# rpi-adapter_V0.net
KiCad netlist of a schematic drawn in EAGLE
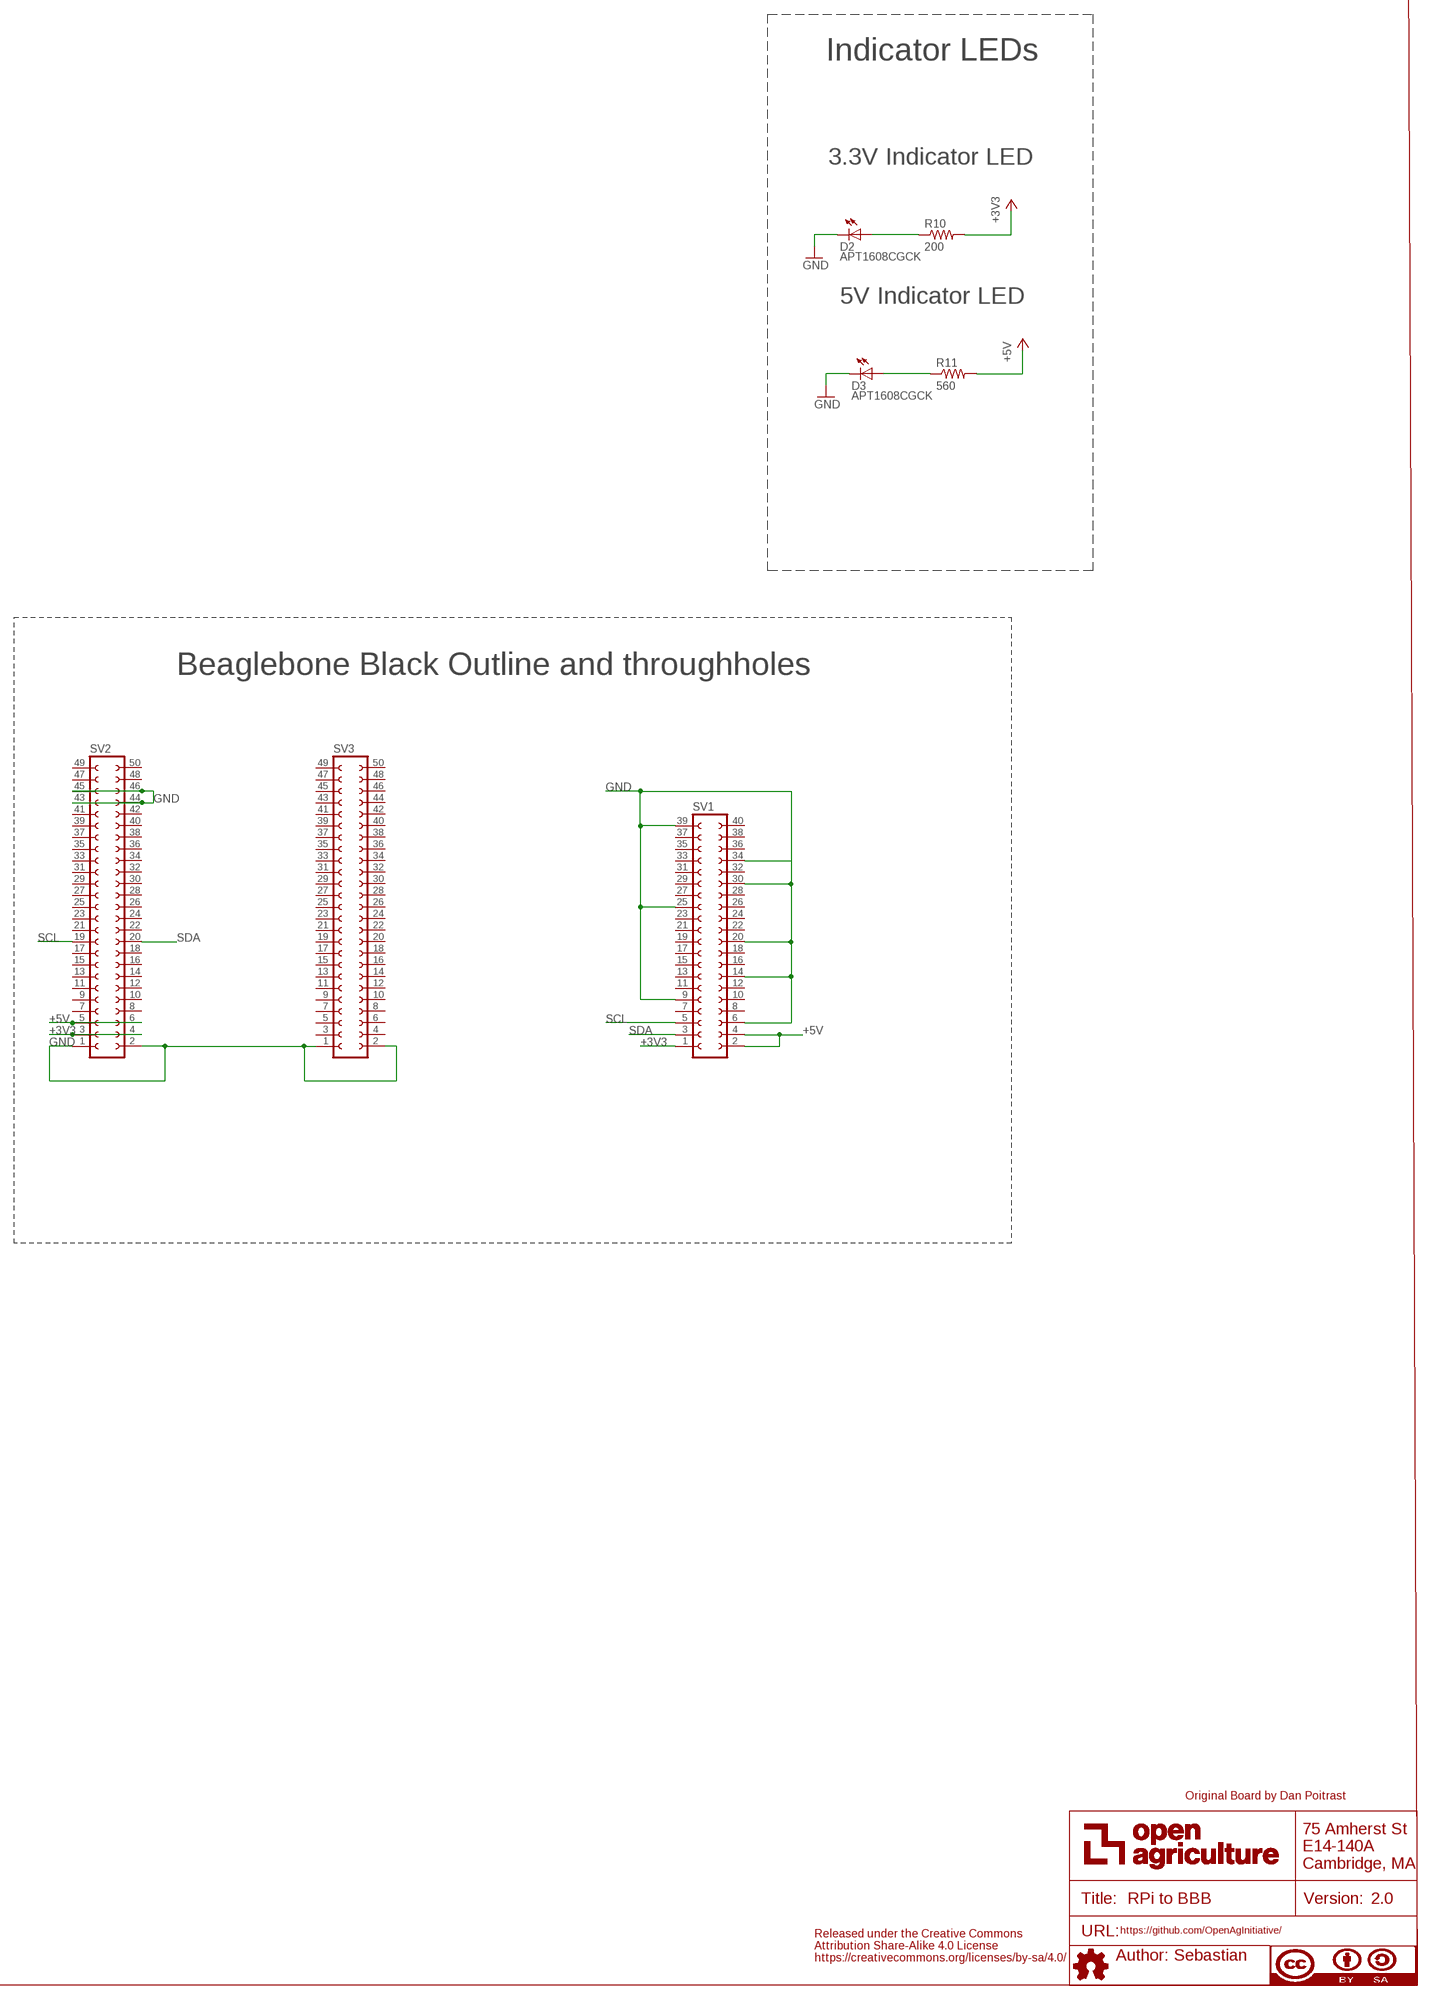
[diagram p0: schematic, sheet 1]

(export (version "E")
  (design (tool "Eeschema 10.0.6"))
  (components
    (comp (ref "ATTRIBUTES")
      (value "DOCFIELD")
      (footprint "eagle-import:DOCFIELD")
      (description "RPi to BBB")
      (fields
        (field (name "TITLE") "Example Template")
        (field (name "AUTHOR") "XX")
        (field (name "VER") "1.0")
        (field (name "URL") "https://github.com/OpenAgInitiative/openag_eagle_template")
        (field (name "AUTHOR_1") "Sebastian")
        (field (name "TITLE_1") "RPi to BBB")
        (field (name "URL_1") "https://github.com/OpenAgInitiative/")
        (field (name "VER_1") "2.0")
      )
      (libsource (lib "eagle-import") (part "DOCFIELD"))
    )
    (comp (ref "D2")
      (value "APT1608CGCK")
      (footprint "eagle-import:CHIPLED_0603")
      (libsource (lib "eagle-import") (part "APT1608CGCK"))
    )
    (comp (ref "D3")
      (value "APT1608CGCK")
      (footprint "eagle-import:CHIPLED_0603")
      (libsource (lib "eagle-import") (part "APT1608CGCK"))
    )
    (comp (ref "R10")
      (value "200")
      (footprint "eagle-import:RC0603N")
      (libsource (lib "eagle-import") (part "100OHM-RC0603JR-07100RL"))
    )
    (comp (ref "R11")
      (value "560")
      (footprint "eagle-import:RC0603N")
      (libsource (lib "eagle-import") (part "100OHM-RC0603JR-07100RL"))
    )
    (comp (ref "SV1")
      (value "FE20-2")
      (footprint "eagle-import:FE20-2")
      (libsource (lib "eagle-import") (part "FE20-2"))
    )
    (comp (ref "SV2")
      (value "FE25-2")
      (footprint "eagle-import:FE25-2")
      (libsource (lib "eagle-import") (part "FE25-2"))
    )
    (comp (ref "SV3")
      (value "FE25-2")
      (footprint "eagle-import:FE25-2")
      (libsource (lib "eagle-import") (part "FE25-2"))
    )
  )
  (nets
    (net (code "1") (name "+3V3") (class "Default")
      (node (ref "R10") (pin "2") (pinfunction "2_2") (pintype "passive"))
      (node (ref "SV1") (pin "1") (pinfunction "1_1") (pintype "passive"))
      (node (ref "SV2") (pin "3") (pinfunction "3_3") (pintype "passive"))
      (node (ref "SV2") (pin "4") (pinfunction "4_4") (pintype "passive"))
    )
    (net (code "2") (name "+5V") (class "Default")
      (node (ref "R11") (pin "2") (pinfunction "2_2") (pintype "passive"))
      (node (ref "SV1") (pin "2") (pinfunction "2_2") (pintype "passive"))
      (node (ref "SV1") (pin "4") (pinfunction "4_4") (pintype "passive"))
      (node (ref "SV2") (pin "5") (pinfunction "5_5") (pintype "passive"))
      (node (ref "SV2") (pin "6") (pinfunction "6_6") (pintype "passive"))
    )
    (net (code "3") (name "/SCL") (class "Default")
      (node (ref "SV1") (pin "5") (pinfunction "5_5") (pintype "passive"))
      (node (ref "SV2") (pin "19") (pinfunction "19_19") (pintype "passive"))
    )
    (net (code "4") (name "/SDA") (class "Default")
      (node (ref "SV1") (pin "3") (pinfunction "3_3") (pintype "passive"))
      (node (ref "SV2") (pin "20") (pinfunction "20_20") (pintype "passive"))
    )
    (net (code "5") (name "GND") (class "Default")
      (node (ref "D2") (pin "C") (pinfunction "C_C") (pintype "passive"))
      (node (ref "D3") (pin "C") (pinfunction "C_C") (pintype "passive"))
      (node (ref "SV1") (pin "14") (pinfunction "14_14") (pintype "passive"))
      (node (ref "SV1") (pin "20") (pinfunction "20_20") (pintype "passive"))
      (node (ref "SV1") (pin "25") (pinfunction "25_25") (pintype "passive"))
      (node (ref "SV1") (pin "30") (pinfunction "30_30") (pintype "passive"))
      (node (ref "SV1") (pin "34") (pinfunction "34_34") (pintype "passive"))
      (node (ref "SV1") (pin "39") (pinfunction "39_39") (pintype "passive"))
      (node (ref "SV1") (pin "6") (pinfunction "6_6") (pintype "passive"))
      (node (ref "SV1") (pin "9") (pinfunction "9_9") (pintype "passive"))
      (node (ref "SV2") (pin "1") (pinfunction "1_1") (pintype "passive"))
      (node (ref "SV2") (pin "2") (pinfunction "2_2") (pintype "passive"))
      (node (ref "SV2") (pin "43") (pinfunction "43_43") (pintype "passive"))
      (node (ref "SV2") (pin "44") (pinfunction "44_44") (pintype "passive"))
      (node (ref "SV2") (pin "45") (pinfunction "45_45") (pintype "passive"))
      (node (ref "SV2") (pin "46") (pinfunction "46_46") (pintype "passive"))
      (node (ref "SV3") (pin "1") (pinfunction "1_1") (pintype "passive"))
      (node (ref "SV3") (pin "2") (pinfunction "2_2") (pintype "passive"))
    )
    (net (code "6") (name "Net-(D2-PadA)") (class "Default")
      (node (ref "D2") (pin "A") (pinfunction "A_A") (pintype "passive"))
      (node (ref "R10") (pin "1") (pinfunction "1_1") (pintype "passive"))
    )
    (net (code "7") (name "Net-(D3-PadA)") (class "Default")
      (node (ref "D3") (pin "A") (pinfunction "A_A") (pintype "passive"))
      (node (ref "R11") (pin "1") (pinfunction "1_1") (pintype "passive"))
    )
    (net (code "8") (name "unconnected-(SV1-Pad7)") (class "Default")
      (node (ref "SV1") (pin "7") (pinfunction "7_7") (pintype "passive"))
    )
    (net (code "9") (name "unconnected-(SV1-Pad8)") (class "Default")
      (node (ref "SV1") (pin "8") (pinfunction "8_8") (pintype "passive"))
    )
    (net (code "10") (name "unconnected-(SV1-Pad10)") (class "Default")
      (node (ref "SV1") (pin "10") (pinfunction "10_10") (pintype "passive"))
    )
    (net (code "11") (name "unconnected-(SV1-Pad11)") (class "Default")
      (node (ref "SV1") (pin "11") (pinfunction "11_11") (pintype "passive"))
    )
    (net (code "12") (name "unconnected-(SV1-Pad12)") (class "Default")
      (node (ref "SV1") (pin "12") (pinfunction "12_12") (pintype "passive"))
    )
    (net (code "13") (name "unconnected-(SV1-Pad13)") (class "Default")
      (node (ref "SV1") (pin "13") (pinfunction "13_13") (pintype "passive"))
    )
    (net (code "14") (name "unconnected-(SV1-Pad15)") (class "Default")
      (node (ref "SV1") (pin "15") (pinfunction "15_15") (pintype "passive"))
    )
    (net (code "15") (name "unconnected-(SV1-Pad16)") (class "Default")
      (node (ref "SV1") (pin "16") (pinfunction "16_16") (pintype "passive"))
    )
    (net (code "16") (name "unconnected-(SV1-Pad17)") (class "Default")
      (node (ref "SV1") (pin "17") (pinfunction "17_17") (pintype "passive"))
    )
    (net (code "17") (name "unconnected-(SV1-Pad18)") (class "Default")
      (node (ref "SV1") (pin "18") (pinfunction "18_18") (pintype "passive"))
    )
    (net (code "18") (name "unconnected-(SV1-Pad19)") (class "Default")
      (node (ref "SV1") (pin "19") (pinfunction "19_19") (pintype "passive"))
    )
    (net (code "19") (name "unconnected-(SV1-Pad21)") (class "Default")
      (node (ref "SV1") (pin "21") (pinfunction "21_21") (pintype "passive"))
    )
    (net (code "20") (name "unconnected-(SV1-Pad22)") (class "Default")
      (node (ref "SV1") (pin "22") (pinfunction "22_22") (pintype "passive"))
    )
    (net (code "21") (name "unconnected-(SV1-Pad23)") (class "Default")
      (node (ref "SV1") (pin "23") (pinfunction "23_23") (pintype "passive"))
    )
    (net (code "22") (name "unconnected-(SV1-Pad24)") (class "Default")
      (node (ref "SV1") (pin "24") (pinfunction "24_24") (pintype "passive"))
    )
    (net (code "23") (name "unconnected-(SV1-Pad26)") (class "Default")
      (node (ref "SV1") (pin "26") (pinfunction "26_26") (pintype "passive"))
    )
    (net (code "24") (name "unconnected-(SV1-Pad27)") (class "Default")
      (node (ref "SV1") (pin "27") (pinfunction "27_27") (pintype "passive"))
    )
    (net (code "25") (name "unconnected-(SV1-Pad28)") (class "Default")
      (node (ref "SV1") (pin "28") (pinfunction "28_28") (pintype "passive"))
    )
    (net (code "26") (name "unconnected-(SV1-Pad29)") (class "Default")
      (node (ref "SV1") (pin "29") (pinfunction "29_29") (pintype "passive"))
    )
    (net (code "27") (name "unconnected-(SV1-Pad31)") (class "Default")
      (node (ref "SV1") (pin "31") (pinfunction "31_31") (pintype "passive"))
    )
    (net (code "28") (name "unconnected-(SV1-Pad32)") (class "Default")
      (node (ref "SV1") (pin "32") (pinfunction "32_32") (pintype "passive"))
    )
    (net (code "29") (name "unconnected-(SV1-Pad33)") (class "Default")
      (node (ref "SV1") (pin "33") (pinfunction "33_33") (pintype "passive"))
    )
    (net (code "30") (name "unconnected-(SV1-Pad35)") (class "Default")
      (node (ref "SV1") (pin "35") (pinfunction "35_35") (pintype "passive"))
    )
    (net (code "31") (name "unconnected-(SV1-Pad36)") (class "Default")
      (node (ref "SV1") (pin "36") (pinfunction "36_36") (pintype "passive"))
    )
    (net (code "32") (name "unconnected-(SV1-Pad37)") (class "Default")
      (node (ref "SV1") (pin "37") (pinfunction "37_37") (pintype "passive"))
    )
    (net (code "33") (name "unconnected-(SV1-Pad38)") (class "Default")
      (node (ref "SV1") (pin "38") (pinfunction "38_38") (pintype "passive"))
    )
    (net (code "34") (name "unconnected-(SV1-Pad40)") (class "Default")
      (node (ref "SV1") (pin "40") (pinfunction "40_40") (pintype "passive"))
    )
    (net (code "35") (name "unconnected-(SV2-Pad7)") (class "Default")
      (node (ref "SV2") (pin "7") (pinfunction "7_7") (pintype "passive"))
    )
    (net (code "36") (name "unconnected-(SV2-Pad8)") (class "Default")
      (node (ref "SV2") (pin "8") (pinfunction "8_8") (pintype "passive"))
    )
    (net (code "37") (name "unconnected-(SV2-Pad9)") (class "Default")
      (node (ref "SV2") (pin "9") (pinfunction "9_9") (pintype "passive"))
    )
    (net (code "38") (name "unconnected-(SV2-Pad10)") (class "Default")
      (node (ref "SV2") (pin "10") (pinfunction "10_10") (pintype "passive"))
    )
    (net (code "39") (name "unconnected-(SV2-Pad11)") (class "Default")
      (node (ref "SV2") (pin "11") (pinfunction "11_11") (pintype "passive"))
    )
    (net (code "40") (name "unconnected-(SV2-Pad12)") (class "Default")
      (node (ref "SV2") (pin "12") (pinfunction "12_12") (pintype "passive"))
    )
    (net (code "41") (name "unconnected-(SV2-Pad13)") (class "Default")
      (node (ref "SV2") (pin "13") (pinfunction "13_13") (pintype "passive"))
    )
    (net (code "42") (name "unconnected-(SV2-Pad14)") (class "Default")
      (node (ref "SV2") (pin "14") (pinfunction "14_14") (pintype "passive"))
    )
    (net (code "43") (name "unconnected-(SV2-Pad15)") (class "Default")
      (node (ref "SV2") (pin "15") (pinfunction "15_15") (pintype "passive"))
    )
    (net (code "44") (name "unconnected-(SV2-Pad16)") (class "Default")
      (node (ref "SV2") (pin "16") (pinfunction "16_16") (pintype "passive"))
    )
    (net (code "45") (name "unconnected-(SV2-Pad17)") (class "Default")
      (node (ref "SV2") (pin "17") (pinfunction "17_17") (pintype "passive"))
    )
    (net (code "46") (name "unconnected-(SV2-Pad18)") (class "Default")
      (node (ref "SV2") (pin "18") (pinfunction "18_18") (pintype "passive"))
    )
    (net (code "47") (name "unconnected-(SV2-Pad21)") (class "Default")
      (node (ref "SV2") (pin "21") (pinfunction "21_21") (pintype "passive"))
    )
    (net (code "48") (name "unconnected-(SV2-Pad22)") (class "Default")
      (node (ref "SV2") (pin "22") (pinfunction "22_22") (pintype "passive"))
    )
    (net (code "49") (name "unconnected-(SV2-Pad23)") (class "Default")
      (node (ref "SV2") (pin "23") (pinfunction "23_23") (pintype "passive"))
    )
    (net (code "50") (name "unconnected-(SV2-Pad24)") (class "Default")
      (node (ref "SV2") (pin "24") (pinfunction "24_24") (pintype "passive"))
    )
    (net (code "51") (name "unconnected-(SV2-Pad25)") (class "Default")
      (node (ref "SV2") (pin "25") (pinfunction "25_25") (pintype "passive"))
    )
    (net (code "52") (name "unconnected-(SV2-Pad26)") (class "Default")
      (node (ref "SV2") (pin "26") (pinfunction "26_26") (pintype "passive"))
    )
    (net (code "53") (name "unconnected-(SV2-Pad27)") (class "Default")
      (node (ref "SV2") (pin "27") (pinfunction "27_27") (pintype "passive"))
    )
    (net (code "54") (name "unconnected-(SV2-Pad28)") (class "Default")
      (node (ref "SV2") (pin "28") (pinfunction "28_28") (pintype "passive"))
    )
    (net (code "55") (name "unconnected-(SV2-Pad29)") (class "Default")
      (node (ref "SV2") (pin "29") (pinfunction "29_29") (pintype "passive"))
    )
    (net (code "56") (name "unconnected-(SV2-Pad30)") (class "Default")
      (node (ref "SV2") (pin "30") (pinfunction "30_30") (pintype "passive"))
    )
    (net (code "57") (name "unconnected-(SV2-Pad31)") (class "Default")
      (node (ref "SV2") (pin "31") (pinfunction "31_31") (pintype "passive"))
    )
    (net (code "58") (name "unconnected-(SV2-Pad32)") (class "Default")
      (node (ref "SV2") (pin "32") (pinfunction "32_32") (pintype "passive"))
    )
    (net (code "59") (name "unconnected-(SV2-Pad33)") (class "Default")
      (node (ref "SV2") (pin "33") (pinfunction "33_33") (pintype "passive"))
    )
    (net (code "60") (name "unconnected-(SV2-Pad34)") (class "Default")
      (node (ref "SV2") (pin "34") (pinfunction "34_34") (pintype "passive"))
    )
    (net (code "61") (name "unconnected-(SV2-Pad35)") (class "Default")
      (node (ref "SV2") (pin "35") (pinfunction "35_35") (pintype "passive"))
    )
    (net (code "62") (name "unconnected-(SV2-Pad36)") (class "Default")
      (node (ref "SV2") (pin "36") (pinfunction "36_36") (pintype "passive"))
    )
    (net (code "63") (name "unconnected-(SV2-Pad37)") (class "Default")
      (node (ref "SV2") (pin "37") (pinfunction "37_37") (pintype "passive"))
    )
    (net (code "64") (name "unconnected-(SV2-Pad38)") (class "Default")
      (node (ref "SV2") (pin "38") (pinfunction "38_38") (pintype "passive"))
    )
    (net (code "65") (name "unconnected-(SV2-Pad39)") (class "Default")
      (node (ref "SV2") (pin "39") (pinfunction "39_39") (pintype "passive"))
    )
    (net (code "66") (name "unconnected-(SV2-Pad40)") (class "Default")
      (node (ref "SV2") (pin "40") (pinfunction "40_40") (pintype "passive"))
    )
    (net (code "67") (name "unconnected-(SV2-Pad41)") (class "Default")
      (node (ref "SV2") (pin "41") (pinfunction "41_41") (pintype "passive"))
    )
    (net (code "68") (name "unconnected-(SV2-Pad42)") (class "Default")
      (node (ref "SV2") (pin "42") (pinfunction "42_42") (pintype "passive"))
    )
    (net (code "69") (name "unconnected-(SV2-Pad47)") (class "Default")
      (node (ref "SV2") (pin "47") (pinfunction "47_47") (pintype "passive"))
    )
    (net (code "70") (name "unconnected-(SV2-Pad48)") (class "Default")
      (node (ref "SV2") (pin "48") (pinfunction "48_48") (pintype "passive"))
    )
    (net (code "71") (name "unconnected-(SV2-Pad49)") (class "Default")
      (node (ref "SV2") (pin "49") (pinfunction "49_49") (pintype "passive"))
    )
    (net (code "72") (name "unconnected-(SV2-Pad50)") (class "Default")
      (node (ref "SV2") (pin "50") (pinfunction "50_50") (pintype "passive"))
    )
    (net (code "73") (name "unconnected-(SV3-Pad3)") (class "Default")
      (node (ref "SV3") (pin "3") (pinfunction "3_3") (pintype "passive"))
    )
    (net (code "74") (name "unconnected-(SV3-Pad4)") (class "Default")
      (node (ref "SV3") (pin "4") (pinfunction "4_4") (pintype "passive"))
    )
    (net (code "75") (name "unconnected-(SV3-Pad5)") (class "Default")
      (node (ref "SV3") (pin "5") (pinfunction "5_5") (pintype "passive"))
    )
    (net (code "76") (name "unconnected-(SV3-Pad6)") (class "Default")
      (node (ref "SV3") (pin "6") (pinfunction "6_6") (pintype "passive"))
    )
    (net (code "77") (name "unconnected-(SV3-Pad7)") (class "Default")
      (node (ref "SV3") (pin "7") (pinfunction "7_7") (pintype "passive"))
    )
    (net (code "78") (name "unconnected-(SV3-Pad8)") (class "Default")
      (node (ref "SV3") (pin "8") (pinfunction "8_8") (pintype "passive"))
    )
    (net (code "79") (name "unconnected-(SV3-Pad9)") (class "Default")
      (node (ref "SV3") (pin "9") (pinfunction "9_9") (pintype "passive"))
    )
    (net (code "80") (name "unconnected-(SV3-Pad10)") (class "Default")
      (node (ref "SV3") (pin "10") (pinfunction "10_10") (pintype "passive"))
    )
    (net (code "81") (name "unconnected-(SV3-Pad11)") (class "Default")
      (node (ref "SV3") (pin "11") (pinfunction "11_11") (pintype "passive"))
    )
    (net (code "82") (name "unconnected-(SV3-Pad12)") (class "Default")
      (node (ref "SV3") (pin "12") (pinfunction "12_12") (pintype "passive"))
    )
    (net (code "83") (name "unconnected-(SV3-Pad13)") (class "Default")
      (node (ref "SV3") (pin "13") (pinfunction "13_13") (pintype "passive"))
    )
    (net (code "84") (name "unconnected-(SV3-Pad14)") (class "Default")
      (node (ref "SV3") (pin "14") (pinfunction "14_14") (pintype "passive"))
    )
    (net (code "85") (name "unconnected-(SV3-Pad15)") (class "Default")
      (node (ref "SV3") (pin "15") (pinfunction "15_15") (pintype "passive"))
    )
    (net (code "86") (name "unconnected-(SV3-Pad16)") (class "Default")
      (node (ref "SV3") (pin "16") (pinfunction "16_16") (pintype "passive"))
    )
    (net (code "87") (name "unconnected-(SV3-Pad17)") (class "Default")
      (node (ref "SV3") (pin "17") (pinfunction "17_17") (pintype "passive"))
    )
    (net (code "88") (name "unconnected-(SV3-Pad18)") (class "Default")
      (node (ref "SV3") (pin "18") (pinfunction "18_18") (pintype "passive"))
    )
    (net (code "89") (name "unconnected-(SV3-Pad19)") (class "Default")
      (node (ref "SV3") (pin "19") (pinfunction "19_19") (pintype "passive"))
    )
    (net (code "90") (name "unconnected-(SV3-Pad20)") (class "Default")
      (node (ref "SV3") (pin "20") (pinfunction "20_20") (pintype "passive"))
    )
    (net (code "91") (name "unconnected-(SV3-Pad21)") (class "Default")
      (node (ref "SV3") (pin "21") (pinfunction "21_21") (pintype "passive"))
    )
    (net (code "92") (name "unconnected-(SV3-Pad22)") (class "Default")
      (node (ref "SV3") (pin "22") (pinfunction "22_22") (pintype "passive"))
    )
    (net (code "93") (name "unconnected-(SV3-Pad23)") (class "Default")
      (node (ref "SV3") (pin "23") (pinfunction "23_23") (pintype "passive"))
    )
    (net (code "94") (name "unconnected-(SV3-Pad24)") (class "Default")
      (node (ref "SV3") (pin "24") (pinfunction "24_24") (pintype "passive"))
    )
    (net (code "95") (name "unconnected-(SV3-Pad25)") (class "Default")
      (node (ref "SV3") (pin "25") (pinfunction "25_25") (pintype "passive"))
    )
    (net (code "96") (name "unconnected-(SV3-Pad26)") (class "Default")
      (node (ref "SV3") (pin "26") (pinfunction "26_26") (pintype "passive"))
    )
    (net (code "97") (name "unconnected-(SV3-Pad27)") (class "Default")
      (node (ref "SV3") (pin "27") (pinfunction "27_27") (pintype "passive"))
    )
    (net (code "98") (name "unconnected-(SV3-Pad28)") (class "Default")
      (node (ref "SV3") (pin "28") (pinfunction "28_28") (pintype "passive"))
    )
    (net (code "99") (name "unconnected-(SV3-Pad29)") (class "Default")
      (node (ref "SV3") (pin "29") (pinfunction "29_29") (pintype "passive"))
    )
    (net (code "100") (name "unconnected-(SV3-Pad30)") (class "Default")
      (node (ref "SV3") (pin "30") (pinfunction "30_30") (pintype "passive"))
    )
    (net (code "101") (name "unconnected-(SV3-Pad31)") (class "Default")
      (node (ref "SV3") (pin "31") (pinfunction "31_31") (pintype "passive"))
    )
    (net (code "102") (name "unconnected-(SV3-Pad32)") (class "Default")
      (node (ref "SV3") (pin "32") (pinfunction "32_32") (pintype "passive"))
    )
    (net (code "103") (name "unconnected-(SV3-Pad33)") (class "Default")
      (node (ref "SV3") (pin "33") (pinfunction "33_33") (pintype "passive"))
    )
    (net (code "104") (name "unconnected-(SV3-Pad34)") (class "Default")
      (node (ref "SV3") (pin "34") (pinfunction "34_34") (pintype "passive"))
    )
    (net (code "105") (name "unconnected-(SV3-Pad35)") (class "Default")
      (node (ref "SV3") (pin "35") (pinfunction "35_35") (pintype "passive"))
    )
    (net (code "106") (name "unconnected-(SV3-Pad36)") (class "Default")
      (node (ref "SV3") (pin "36") (pinfunction "36_36") (pintype "passive"))
    )
    (net (code "107") (name "unconnected-(SV3-Pad37)") (class "Default")
      (node (ref "SV3") (pin "37") (pinfunction "37_37") (pintype "passive"))
    )
    (net (code "108") (name "unconnected-(SV3-Pad38)") (class "Default")
      (node (ref "SV3") (pin "38") (pinfunction "38_38") (pintype "passive"))
    )
    (net (code "109") (name "unconnected-(SV3-Pad39)") (class "Default")
      (node (ref "SV3") (pin "39") (pinfunction "39_39") (pintype "passive"))
    )
    (net (code "110") (name "unconnected-(SV3-Pad40)") (class "Default")
      (node (ref "SV3") (pin "40") (pinfunction "40_40") (pintype "passive"))
    )
    (net (code "111") (name "unconnected-(SV3-Pad41)") (class "Default")
      (node (ref "SV3") (pin "41") (pinfunction "41_41") (pintype "passive"))
    )
    (net (code "112") (name "unconnected-(SV3-Pad42)") (class "Default")
      (node (ref "SV3") (pin "42") (pinfunction "42_42") (pintype "passive"))
    )
    (net (code "113") (name "unconnected-(SV3-Pad43)") (class "Default")
      (node (ref "SV3") (pin "43") (pinfunction "43_43") (pintype "passive"))
    )
    (net (code "114") (name "unconnected-(SV3-Pad44)") (class "Default")
      (node (ref "SV3") (pin "44") (pinfunction "44_44") (pintype "passive"))
    )
    (net (code "115") (name "unconnected-(SV3-Pad45)") (class "Default")
      (node (ref "SV3") (pin "45") (pinfunction "45_45") (pintype "passive"))
    )
    (net (code "116") (name "unconnected-(SV3-Pad46)") (class "Default")
      (node (ref "SV3") (pin "46") (pinfunction "46_46") (pintype "passive"))
    )
    (net (code "117") (name "unconnected-(SV3-Pad47)") (class "Default")
      (node (ref "SV3") (pin "47") (pinfunction "47_47") (pintype "passive"))
    )
    (net (code "118") (name "unconnected-(SV3-Pad48)") (class "Default")
      (node (ref "SV3") (pin "48") (pinfunction "48_48") (pintype "passive"))
    )
    (net (code "119") (name "unconnected-(SV3-Pad49)") (class "Default")
      (node (ref "SV3") (pin "49") (pinfunction "49_49") (pintype "passive"))
    )
    (net (code "120") (name "unconnected-(SV3-Pad50)") (class "Default")
      (node (ref "SV3") (pin "50") (pinfunction "50_50") (pintype "passive"))
    )
  )
)
